# Connectors.net
KiCad netlist of a schematic drawn in Altium Designer
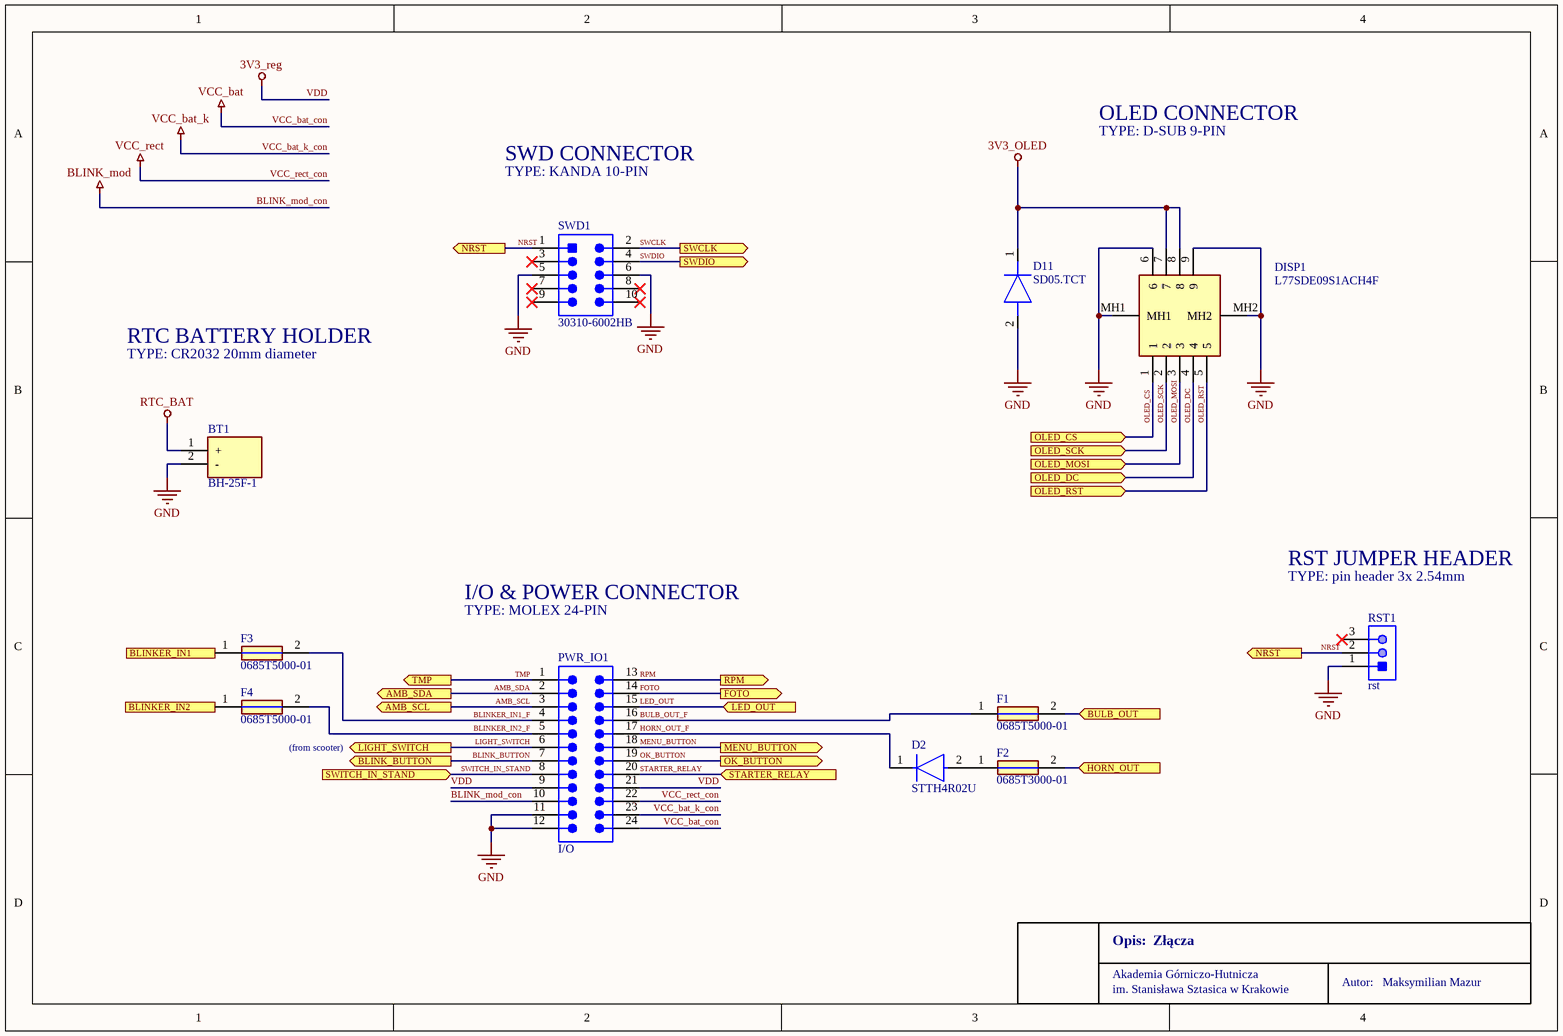
[diagram p0: Connectors.SchDoc]

(export (version "E")
  (design (tool "Eeschema 10.0.6"))
  (components
    (comp (ref "BT1")
      (value "BH-25F-1")
      (footprint "SamacSys:BH25F1")
      (description "Battery")
      (fields (field (name "MOUSER PART NUMBER") "737-BH-25F-1"))
      (libsource (lib "*") (part "BH-25F-1"))
    )
    (comp (ref "D2")
      (value "STTH4R02U")
      (footprint "FP-SMB-MFG")
      (description "DIODE GEN PURP 200V 4A SMB")
      (fields
        (field (name "MANUFACTURER") "STMicroelectronics")
        (field (name "OCTOPART") "https://octopart.com/stth4r02u-stmicroelectronics-324581")
      )
      (libsource (lib "Altium Content Vault") (part "bbad89a4e1b75021f221062c6e04887"))
    )
    (comp (ref "D11")
      (value "SD05.TCT")
      (footprint "SamacSys:SOD2513X110N")
      (description "Diode")
      (fields (field (name "MOUSER PART NUMBER") "947-SD05.TCT"))
      (libsource (lib "*") (part "SD05.TCT"))
    )
    (comp (ref "DISP1")
      (value "L77SDE09S1ACH4F")
      (footprint "SamacSys:L77SDE09S1ACH4F")
      (description "Connector")
      (fields (field (name "MOUSER PART NUMBER") "523-L77SDE09S1ACH4F"))
      (libsource (lib "*") (part "L77SDE09S1ACH4F"))
    )
    (comp (ref "F1")
      (value "0685T5000-01")
      (footprint "SamacSys:FUSC3216X83N")
      (description "Fuse 5A \r\n63VAC/63VDC\r\n1206")
      (fields (field (name "MANUFACTURER_PART_NUMBER") "0685T3000-01"))
      (libsource (lib "*") (part "0685T3000-01"))
    )
    (comp (ref "F2")
      (value "0685T3000-01")
      (footprint "SamacSys:FUSC3216X83N")
      (description "Fuse 3A \r\n63VAC/63VDC\r\n1206")
      (libsource (lib "*") (part "0685T3000-01"))
    )
    (comp (ref "F3")
      (value "0685T5000-01")
      (footprint "SamacSys:FUSC3216X83N")
      (description "Fuse 5A \r\n63VAC/63VDC\r\n1206")
      (fields (field (name "MANUFACTURER_PART_NUMBER") "0685T3000-01"))
      (libsource (lib "*") (part "0685T3000-01"))
    )
    (comp (ref "F4")
      (value "0685T5000-01")
      (footprint "SamacSys:FUSC3216X83N")
      (description "Fuse 5A \r\n63VAC/63VDC\r\n1206")
      (fields (field (name "MANUFACTURER_PART_NUMBER") "0685T3000-01"))
      (libsource (lib "*") (part "0685T3000-01"))
    )
    (comp (ref "PWR_IO1")
      (value "I/O")
      (footprint "649024227222")
      (libsource (lib "Altium Content Vault") (part "Header_Male_2R_24P(A)"))
    )
    (comp (ref "RST1")
      (value "rst")
      (footprint "MOLX-22-28-4033_V")
      (description "Male Header, Pitch 2.54 mm, 1 x 3 Position, Height 8.38 mm, Tail Length 3.18 mm, RoHS, Bulk")
      (fields (field (name "MANUFACTURER") "Molex"))
      (libsource (lib "Altium Content Vault") (part "CN-1P-M-R3"))
    )
    (comp (ref "SWD1")
      (value "30310-6002HB")
      (footprint "3M-30310-6002HB-10_V")
      (fields (field (name "MANUFACTURER") "3M"))
      (libsource (lib "Altium Content Vault") (part "CN-2P-M-R10"))
    )
  )
  (nets
    (net (code "1") (name "/AMB_SCL") (class "Default")
      (node (ref "PWR_IO1") (pin "3") (pinfunction "3_3") (pintype "passive"))
    )
    (net (code "2") (name "/AMB_SDA") (class "Default")
      (node (ref "PWR_IO1") (pin "2") (pinfunction "2_2") (pintype "passive"))
    )
    (net (code "3") (name "/BLINKER_IN1") (class "Default")
      (node (ref "F3") (pin "1") (pinfunction "1_1") (pintype "passive"))
    )
    (net (code "4") (name "/BLINKER_IN1_F") (class "Default")
      (node (ref "F3") (pin "2") (pinfunction "2_2") (pintype "passive"))
      (node (ref "PWR_IO1") (pin "4") (pinfunction "4_4") (pintype "passive"))
    )
    (net (code "5") (name "/BLINKER_IN2") (class "Default")
      (node (ref "F4") (pin "1") (pinfunction "1_1") (pintype "passive"))
    )
    (net (code "6") (name "/BLINKER_IN2_F") (class "Default")
      (node (ref "F4") (pin "2") (pinfunction "2_2") (pintype "passive"))
      (node (ref "PWR_IO1") (pin "5") (pinfunction "5_5") (pintype "passive"))
    )
    (net (code "7") (name "/BLINK_BUTTON") (class "Default")
      (node (ref "PWR_IO1") (pin "7") (pinfunction "7_7") (pintype "passive"))
    )
    (net (code "8") (name "/BULB_OUT") (class "Default")
      (node (ref "F1") (pin "2") (pinfunction "2_2") (pintype "passive"))
    )
    (net (code "9") (name "/BULB_OUT_F") (class "Default")
      (node (ref "F1") (pin "1") (pinfunction "1_1") (pintype "passive"))
      (node (ref "PWR_IO1") (pin "16") (pinfunction "16_16") (pintype "passive"))
    )
    (net (code "10") (name "/FOTO") (class "Default")
      (node (ref "PWR_IO1") (pin "14") (pinfunction "14_14") (pintype "passive"))
    )
    (net (code "11") (name "/HORN_OUT") (class "Default")
      (node (ref "F2") (pin "2") (pinfunction "2_2") (pintype "passive"))
    )
    (net (code "12") (name "/HORN_OUT_F") (class "Default")
      (node (ref "D2") (pin "1") (pinfunction "K_1") (pintype "passive"))
      (node (ref "PWR_IO1") (pin "17") (pinfunction "17_17") (pintype "passive"))
    )
    (net (code "13") (name "/LED_OUT") (class "Default")
      (node (ref "PWR_IO1") (pin "15") (pinfunction "15_15") (pintype "passive"))
    )
    (net (code "14") (name "/LIGHT_SWITCH") (class "Default")
      (node (ref "PWR_IO1") (pin "6") (pinfunction "6_6") (pintype "passive"))
    )
    (net (code "15") (name "/MENU_BUTTON") (class "Default")
      (node (ref "PWR_IO1") (pin "18") (pinfunction "18_18") (pintype "passive"))
    )
    (net (code "16") (name "/NRST") (class "Default")
      (node (ref "RST1") (pin "2") (pinfunction "2_2") (pintype "passive"))
      (node (ref "SWD1") (pin "1") (pinfunction "1_1") (pintype "passive"))
    )
    (net (code "17") (name "/OK_BUTTON") (class "Default")
      (node (ref "PWR_IO1") (pin "19") (pinfunction "19_19") (pintype "passive"))
    )
    (net (code "18") (name "/OLED_CS") (class "Default")
      (node (ref "DISP1") (pin "1") (pinfunction "1_1") (pintype "passive"))
    )
    (net (code "19") (name "/OLED_DC") (class "Default")
      (node (ref "DISP1") (pin "4") (pinfunction "4_4") (pintype "passive"))
    )
    (net (code "20") (name "/OLED_MOSI") (class "Default")
      (node (ref "DISP1") (pin "3") (pinfunction "3_3") (pintype "passive"))
    )
    (net (code "21") (name "/OLED_RST") (class "Default")
      (node (ref "DISP1") (pin "5") (pinfunction "5_5") (pintype "passive"))
    )
    (net (code "22") (name "/OLED_SCK") (class "Default")
      (node (ref "DISP1") (pin "2") (pinfunction "2_2") (pintype "passive"))
    )
    (net (code "23") (name "/RPM") (class "Default")
      (node (ref "PWR_IO1") (pin "13") (pinfunction "13_13") (pintype "passive"))
    )
    (net (code "24") (name "/STARTER_RELAY") (class "Default")
      (node (ref "PWR_IO1") (pin "20") (pinfunction "20_20") (pintype "passive"))
    )
    (net (code "25") (name "/SWCLK") (class "Default")
      (node (ref "SWD1") (pin "2") (pinfunction "2_2") (pintype "passive"))
    )
    (net (code "26") (name "/SWDIO") (class "Default")
      (node (ref "SWD1") (pin "4") (pinfunction "4_4") (pintype "passive"))
    )
    (net (code "27") (name "/SWITCH_IN_STAND") (class "Default")
      (node (ref "PWR_IO1") (pin "8") (pinfunction "8_8") (pintype "passive"))
    )
    (net (code "28") (name "/TMP") (class "Default")
      (node (ref "PWR_IO1") (pin "1") (pinfunction "1_1") (pintype "passive"))
    )
    (net (code "29") (name "3V3_OLED") (class "Default")
      (node (ref "D11") (pin "1") (pinfunction "K_1") (pintype "passive"))
      (node (ref "DISP1") (pin "7") (pinfunction "7_7") (pintype "passive"))
      (node (ref "DISP1") (pin "8") (pinfunction "8_8") (pintype "passive"))
    )
    (net (code "30") (name "3V3_reg") (class "Default")
      (node (ref "PWR_IO1") (pin "21") (pinfunction "21_21") (pintype "passive"))
      (node (ref "PWR_IO1") (pin "9") (pinfunction "9_9") (pintype "passive"))
    )
    (net (code "31") (name "BLINK_mod") (class "Default")
      (node (ref "PWR_IO1") (pin "10") (pinfunction "10_10") (pintype "passive"))
    )
    (net (code "32") (name "GND") (class "Default")
      (node (ref "BT1") (pin "2") (pinfunction "-_2") (pintype "passive"))
      (node (ref "D11") (pin "2") (pinfunction "A_2") (pintype "passive"))
      (node (ref "DISP1") (pin "6") (pinfunction "6_6") (pintype "passive"))
      (node (ref "DISP1") (pin "9") (pinfunction "9_9") (pintype "passive"))
      (node (ref "DISP1") (pin "MH1") (pinfunction "MH1_MH1") (pintype "passive"))
      (node (ref "DISP1") (pin "MH2") (pinfunction "MH2_MH2") (pintype "passive"))
      (node (ref "PWR_IO1") (pin "11") (pinfunction "11_11") (pintype "passive"))
      (node (ref "PWR_IO1") (pin "12") (pinfunction "12_12") (pintype "passive"))
      (node (ref "RST1") (pin "1") (pinfunction "1_1") (pintype "passive"))
      (node (ref "SWD1") (pin "5") (pinfunction "5_5") (pintype "passive"))
      (node (ref "SWD1") (pin "6") (pinfunction "6_6") (pintype "passive"))
    )
    (net (code "33") (name "Net-(D2-A)") (class "Default")
      (node (ref "D2") (pin "2") (pinfunction "A_2") (pintype "passive"))
      (node (ref "F2") (pin "1") (pinfunction "1_1") (pintype "passive"))
    )
    (net (code "34") (name "RTC_BAT") (class "Default")
      (node (ref "BT1") (pin "1") (pinfunction "+_1") (pintype "passive"))
    )
    (net (code "35") (name "VCC_bat") (class "Default")
      (node (ref "PWR_IO1") (pin "24") (pinfunction "24_24") (pintype "passive"))
    )
    (net (code "36") (name "VCC_bat_k") (class "Default")
      (node (ref "PWR_IO1") (pin "23") (pinfunction "23_23") (pintype "passive"))
    )
    (net (code "37") (name "VCC_rect") (class "Default")
      (node (ref "PWR_IO1") (pin "22") (pinfunction "22_22") (pintype "passive"))
    )
    (net (code "38") (name "unconnected-(RST1-Pad3)") (class "Default")
      (node (ref "RST1") (pin "3") (pinfunction "3_3") (pintype "passive+no_connect"))
    )
    (net (code "39") (name "unconnected-(SWD1-Pad3)") (class "Default")
      (node (ref "SWD1") (pin "3") (pinfunction "3_3") (pintype "passive+no_connect"))
    )
    (net (code "40") (name "unconnected-(SWD1-Pad7)") (class "Default")
      (node (ref "SWD1") (pin "7") (pinfunction "7_7") (pintype "passive+no_connect"))
    )
    (net (code "41") (name "unconnected-(SWD1-Pad8)") (class "Default")
      (node (ref "SWD1") (pin "8") (pinfunction "8_8") (pintype "passive+no_connect"))
    )
    (net (code "42") (name "unconnected-(SWD1-Pad9)") (class "Default")
      (node (ref "SWD1") (pin "9") (pinfunction "9_9") (pintype "passive+no_connect"))
    )
    (net (code "43") (name "unconnected-(SWD1-Pad10)") (class "Default")
      (node (ref "SWD1") (pin "10") (pinfunction "10_10") (pintype "passive+no_connect"))
    )
  )
)
